# IRF7317_TR.net
KiCad netlist of a schematic drawn in Altium Designer
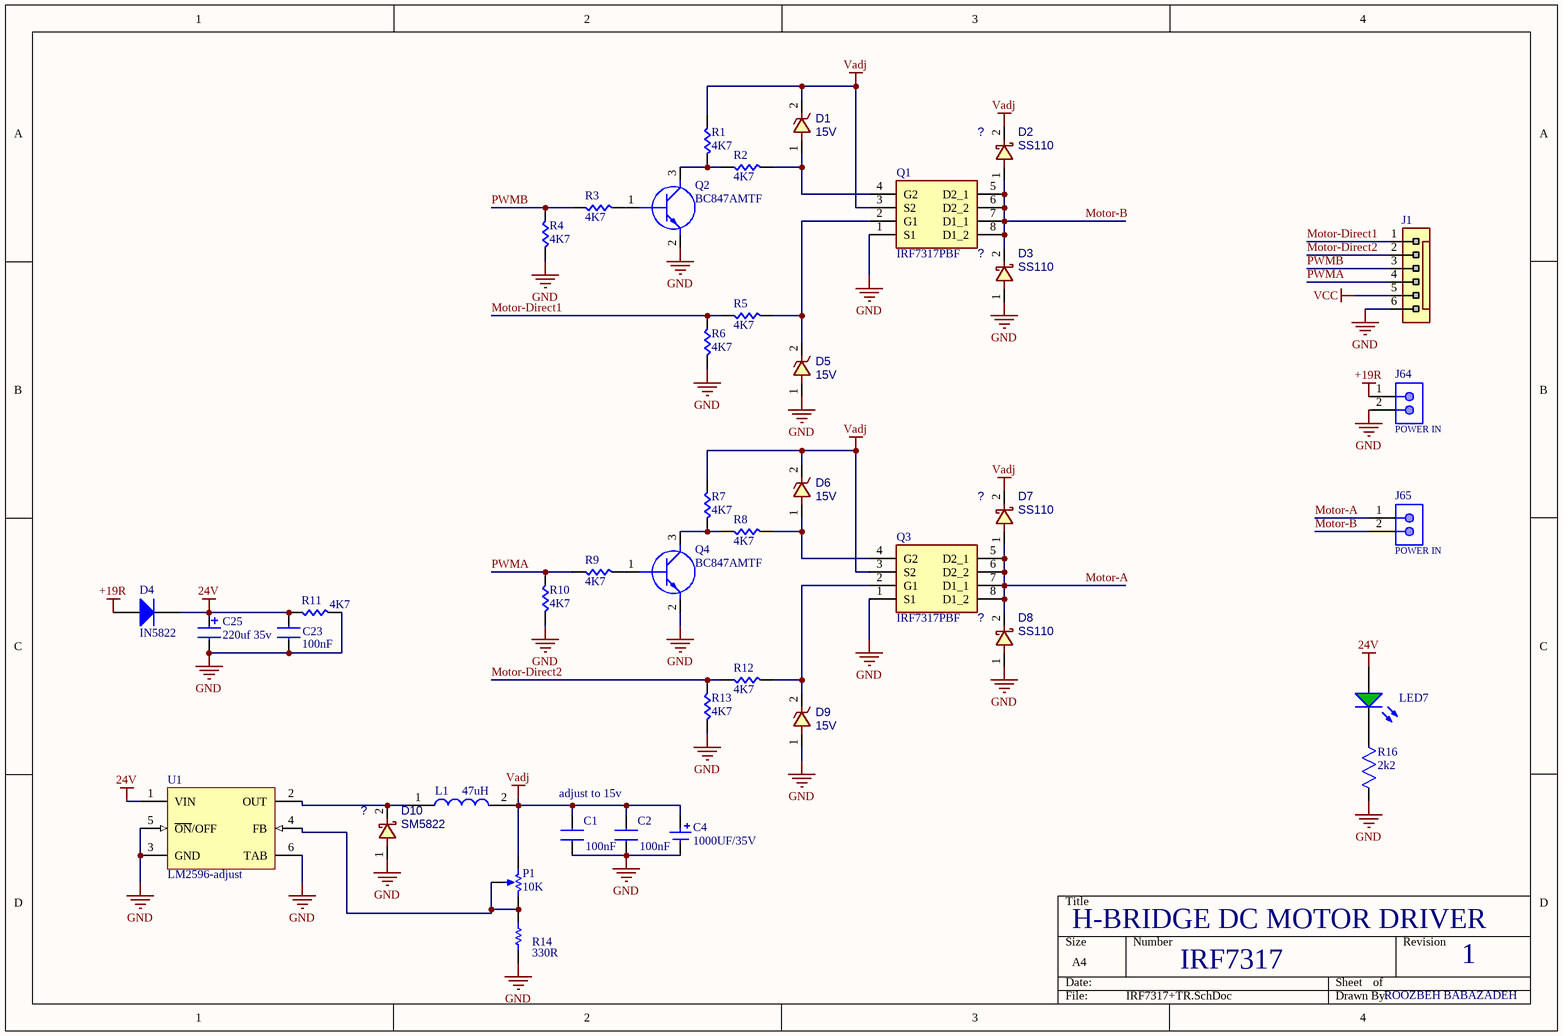
[diagram p0: IRF7317+TR.SchDoc]

(export (version "E")
  (design (tool "Eeschema 10.0.6"))
  (components
    (comp (ref "C1") (value "100nF") (footprint "C0805") (libsource (lib "OTHER") (part "C")))
    (comp (ref "C2") (value "100nF") (footprint "C0805") (libsource (lib "OTHER") (part "C")))
    (comp (ref "C4")
      (value "1000UF/35V")
      (footprint "C_EL_12X25")
      (libsource (lib "OTHER") (part "CAP_ELECTRO_POLIMER"))
    )
    (comp (ref "C23") (value "100nF") (footprint "C0805") (libsource (lib "OTHER") (part "C")))
    (comp (ref "C25") (value "220uf 35v") (footprint "C_EL_10X12") (libsource (lib "OTHER") (part "CAP3528")))
    (comp (ref "D1")
      (value "15V")
      (footprint "D_SOD80")
      (description "DIODE, ZENER, 3W, 5.6V")
      (fields (field (name "MANF") "MCC") (field (name "MANF_P#") "3SMAJ5919B-TP"))
      (libsource (lib "diode") (part "ZENER"))
    )
    (comp (ref "D2")
      (value "SS110")
      (footprint "D_SMA")
      (description "DIODE, SCHOTTKY, 40V, 1A")
      (fields
        (field (name "MANF") "DIODES")
        (field (name "MANF_P#") "1N5819HW-7-F")
        (field (name "ALTIUM_VALUE") "?")
      )
      (libsource (lib "diode") (part "SCHOTTKY"))
    )
    (comp (ref "D3")
      (value "SS110")
      (footprint "D_SMA")
      (description "DIODE, SCHOTTKY, 40V, 1A")
      (fields
        (field (name "MANF") "DIODES")
        (field (name "MANF_P#") "1N5819HW-7-F")
        (field (name "ALTIUM_VALUE") "?")
      )
      (libsource (lib "diode") (part "SCHOTTKY"))
    )
    (comp (ref "D4")
      (value "IN5822")
      (footprint "D_SMB")
      (description "1 Amp General Purpose Rectifier")
      (fields (field (name "PUBLISHER") "Altium Limited"))
      (libsource (lib "Miscellaneous Devices") (part "Diode 1N4005"))
    )
    (comp (ref "D5")
      (value "15V")
      (footprint "D_SOD80")
      (description "DIODE, ZENER, 3W, 5.6V")
      (fields (field (name "MANF") "MCC") (field (name "MANF_P#") "3SMAJ5919B-TP"))
      (libsource (lib "diode") (part "ZENER"))
    )
    (comp (ref "D6")
      (value "15V")
      (footprint "D_SOD80")
      (description "DIODE, ZENER, 3W, 5.6V")
      (fields (field (name "MANF") "MCC") (field (name "MANF_P#") "3SMAJ5919B-TP"))
      (libsource (lib "diode") (part "ZENER"))
    )
    (comp (ref "D7")
      (value "SS110")
      (footprint "D_SMA")
      (description "DIODE, SCHOTTKY, 40V, 1A")
      (fields
        (field (name "MANF") "DIODES")
        (field (name "MANF_P#") "1N5819HW-7-F")
        (field (name "ALTIUM_VALUE") "?")
      )
      (libsource (lib "diode") (part "SCHOTTKY"))
    )
    (comp (ref "D8")
      (value "SS110")
      (footprint "D_SMA")
      (description "DIODE, SCHOTTKY, 40V, 1A")
      (fields
        (field (name "MANF") "DIODES")
        (field (name "MANF_P#") "1N5819HW-7-F")
        (field (name "ALTIUM_VALUE") "?")
      )
      (libsource (lib "diode") (part "SCHOTTKY"))
    )
    (comp (ref "D9")
      (value "15V")
      (footprint "D_SOD80")
      (description "DIODE, ZENER, 3W, 5.6V")
      (fields (field (name "MANF") "MCC") (field (name "MANF_P#") "3SMAJ5919B-TP"))
      (libsource (lib "diode") (part "ZENER"))
    )
    (comp (ref "D10")
      (value "SM5822")
      (footprint "D_SMB")
      (description "DIODE, SCHOTTKY, 40V, 1A")
      (fields
        (field (name "MANF") "DIODES")
        (field (name "MANF_P#") "1N5819HW-7-F")
        (field (name "ALTIUM_VALUE") "?")
      )
      (libsource (lib "diode") (part "SCHOTTKY"))
    )
    (comp (ref "J1")
      (value "HDRWF_6")
      (footprint "WF_6")
      (description "Header, WF, Pitch: 2.54mm")
      (libsource (lib "xh-xhr-wf-hhdr-hh6r") (part "HDRWF_6"))
    )
    (comp (ref "J64")
      (value "POWER IN")
      (footprint "PWL_2")
      (description "WR-PHD Pin Header, THT, pitch 2.54mm, Single Row, Vertical, 2pin")
      (fields (field (name "PART NUMBER") "61300211121") (field (name "PUBLISHER") "Wurth Elektronik"))
      (libsource (lib "sip m") (part "sip 2"))
    )
    (comp (ref "J65")
      (value "POWER IN")
      (footprint "PWL_2")
      (description "WR-PHD Pin Header, THT, pitch 2.54mm, Single Row, Vertical, 2pin")
      (fields (field (name "PART NUMBER") "61300211121") (field (name "PUBLISHER") "Wurth Elektronik"))
      (libsource (lib "sip m") (part "sip 2"))
    )
    (comp (ref "L1")
      (value "47uH")
      (footprint "CDRH127LDNP560MC-12*12")
      (description "Inductor")
      (fields
        (field (name "MANUFACTURER_PART_NUMBER") "CDRH127/LDNP-560MC")
        (field (name "MOUSER PART NUMBER") "851-CDRH127LDNP560MC")
      )
      (libsource (lib "*") (part "CDRH127_LDNP-560MC"))
    )
    (comp (ref "LED7") (value "~") (footprint "LED1206RED") (libsource (lib "OTHER") (part "LED3mm")))
    (comp (ref "P1")
      (value "10K")
      (footprint "POT_3296W")
      (description "Potentiometer")
      (libsource (lib "My_LIB") (part "Multi-Turn"))
    )
    (comp (ref "Q1")
      (value "IRF7317PBF")
      (footprint "SO_8")
      (description "Transistor")
      (fields (field (name "MOUSER PART NUMBER") "942-IRF7317PBF"))
      (libsource (lib "*") (part "IRF7317PBF"))
    )
    (comp (ref "Q2")
      (value "BC847AMTF")
      (footprint "SOT23")
      (description "Transistor BJT NPN")
      (fields (field (name "MOUSER PART NUMBER") "512-BC847AMTF"))
      (libsource (lib "*") (part "BC847AMTF"))
    )
    (comp (ref "Q3")
      (value "IRF7317PBF")
      (footprint "SO_8")
      (description "Transistor")
      (fields (field (name "MOUSER PART NUMBER") "942-IRF7317PBF"))
      (libsource (lib "*") (part "IRF7317PBF"))
    )
    (comp (ref "Q4")
      (value "BC847AMTF")
      (footprint "SOT23")
      (description "Transistor BJT NPN")
      (fields (field (name "MOUSER PART NUMBER") "512-BC847AMTF"))
      (libsource (lib "*") (part "BC847AMTF"))
    )
    (comp (ref "R1") (value "4K7") (footprint "R0805") (libsource (lib "OTHER") (part "R")))
    (comp (ref "R2") (value "4K7") (footprint "R0805") (libsource (lib "OTHER") (part "R")))
    (comp (ref "R3") (value "4K7") (footprint "R0805") (libsource (lib "OTHER") (part "R")))
    (comp (ref "R4") (value "4K7") (footprint "R0805") (libsource (lib "OTHER") (part "R")))
    (comp (ref "R5") (value "4K7") (footprint "R0805") (libsource (lib "OTHER") (part "R")))
    (comp (ref "R6") (value "4K7") (footprint "R0805") (libsource (lib "OTHER") (part "R")))
    (comp (ref "R7") (value "4K7") (footprint "R0805") (libsource (lib "OTHER") (part "R")))
    (comp (ref "R8") (value "4K7") (footprint "R0805") (libsource (lib "OTHER") (part "R")))
    (comp (ref "R9") (value "4K7") (footprint "R0805") (libsource (lib "OTHER") (part "R")))
    (comp (ref "R10") (value "4K7") (footprint "R0805") (libsource (lib "OTHER") (part "R")))
    (comp (ref "R11") (value "4K7") (footprint "R0805") (libsource (lib "OTHER") (part "R")))
    (comp (ref "R12") (value "4K7") (footprint "R0805") (libsource (lib "OTHER") (part "R")))
    (comp (ref "R13") (value "4K7") (footprint "R0805") (libsource (lib "OTHER") (part "R")))
    (comp (ref "R14")
      (value "330R")
      (footprint "R0805")
      (description "Resistor")
      (fields (field (name "PUBLISHER") "Altium Limited"))
      (libsource (lib "Miscellaneous Devices") (part "Res1"))
    )
    (comp (ref "R16") (value "2k2") (footprint "R0805") (libsource (lib "") (part "R_1")))
    (comp (ref "U1")
      (value "LM2596-adjust")
      (footprint "to-263-5 5d2pak LM2596S")
      (libsource (lib "POWER") (part "LM2596s"))
    )
  )
  (nets
    (net (code "1") (name "+19R") (class "Default")
      (node (ref "D4") (pin "1") (pinfunction "A_1") (pintype "passive"))
      (node (ref "J64") (pin "1") (pinfunction "1_1") (pintype "passive"))
    )
    (net (code "2") (name "/Motor-A") (class "Default")
      (node (ref "D7") (pin "1") (pinfunction "1_1") (pintype "passive"))
      (node (ref "D8") (pin "2") (pinfunction "2_2") (pintype "passive"))
      (node (ref "J65") (pin "1") (pinfunction "1_1") (pintype "passive"))
      (node (ref "Q3") (pin "5") (pinfunction "D2_1_5") (pintype "passive"))
      (node (ref "Q3") (pin "6") (pinfunction "D2_2_6") (pintype "passive"))
      (node (ref "Q3") (pin "7") (pinfunction "D1_1_7") (pintype "passive"))
      (node (ref "Q3") (pin "8") (pinfunction "D1_2_8") (pintype "passive"))
    )
    (net (code "3") (name "/Motor-B") (class "Default")
      (node (ref "D2") (pin "1") (pinfunction "1_1") (pintype "passive"))
      (node (ref "D3") (pin "2") (pinfunction "2_2") (pintype "passive"))
      (node (ref "J65") (pin "2") (pinfunction "2_2") (pintype "passive"))
      (node (ref "Q1") (pin "5") (pinfunction "D2_1_5") (pintype "passive"))
      (node (ref "Q1") (pin "6") (pinfunction "D2_2_6") (pintype "passive"))
      (node (ref "Q1") (pin "7") (pinfunction "D1_1_7") (pintype "passive"))
      (node (ref "Q1") (pin "8") (pinfunction "D1_2_8") (pintype "passive"))
    )
    (net (code "4") (name "/Motor-Direct1") (class "Default")
      (node (ref "J1") (pin "1") (pinfunction "1_1") (pintype "passive"))
      (node (ref "R5") (pin "2") (pintype "passive"))
      (node (ref "R6") (pin "1") (pintype "passive"))
    )
    (net (code "5") (name "/Motor-Direct2") (class "Default")
      (node (ref "J1") (pin "2") (pinfunction "2_2") (pintype "passive"))
      (node (ref "R12") (pin "2") (pintype "passive"))
      (node (ref "R13") (pin "1") (pintype "passive"))
    )
    (net (code "6") (name "/PWMA") (class "Default")
      (node (ref "J1") (pin "4") (pinfunction "4_4") (pintype "passive"))
      (node (ref "R10") (pin "2") (pintype "passive"))
      (node (ref "R9") (pin "1") (pintype "passive"))
    )
    (net (code "7") (name "/PWMB") (class "Default")
      (node (ref "J1") (pin "3") (pinfunction "3_3") (pintype "passive"))
      (node (ref "R3") (pin "1") (pintype "passive"))
      (node (ref "R4") (pin "2") (pintype "passive"))
    )
    (net (code "8") (name "24V") (class "Default")
      (node (ref "C23") (pin "2") (pintype "passive"))
      (node (ref "C25") (pin "1") (pinfunction "1_1") (pintype "passive"))
      (node (ref "D4") (pin "2") (pinfunction "K_2") (pintype "passive"))
      (node (ref "LED7") (pin "1") (pinfunction "A_1") (pintype "passive"))
      (node (ref "R11") (pin "2") (pintype "passive"))
      (node (ref "U1") (pin "1") (pinfunction "VIN_1") (pintype "power_in"))
    )
    (net (code "9") (name "GND") (class "Default")
      (node (ref "C1") (pin "1") (pintype "passive"))
      (node (ref "C2") (pin "1") (pintype "passive"))
      (node (ref "C23") (pin "1") (pintype "passive"))
      (node (ref "C25") (pin "2") (pinfunction "2_2") (pintype "passive"))
      (node (ref "C4") (pin "2") (pinfunction "2_2") (pintype "passive"))
      (node (ref "D10") (pin "1") (pinfunction "1_1") (pintype "passive"))
      (node (ref "D3") (pin "1") (pinfunction "1_1") (pintype "passive"))
      (node (ref "D5") (pin "1") (pinfunction "1_1") (pintype "passive"))
      (node (ref "D8") (pin "1") (pinfunction "1_1") (pintype "passive"))
      (node (ref "D9") (pin "1") (pinfunction "1_1") (pintype "passive"))
      (node (ref "J1") (pin "6") (pinfunction "6_6") (pintype "passive"))
      (node (ref "J64") (pin "2") (pinfunction "2_2") (pintype "passive"))
      (node (ref "Q1") (pin "1") (pinfunction "S1_1") (pintype "passive"))
      (node (ref "Q2") (pin "2") (pinfunction "E_2") (pintype "passive"))
      (node (ref "Q3") (pin "1") (pinfunction "S1_1") (pintype "passive"))
      (node (ref "Q4") (pin "2") (pinfunction "E_2") (pintype "passive"))
      (node (ref "R10") (pin "1") (pintype "passive"))
      (node (ref "R11") (pin "1") (pintype "passive"))
      (node (ref "R13") (pin "2") (pintype "passive"))
      (node (ref "R14") (pin "1") (pinfunction "1_1") (pintype "passive"))
      (node (ref "R16") (pin "2") (pintype "passive"))
      (node (ref "R4") (pin "1") (pintype "passive"))
      (node (ref "R6") (pin "2") (pintype "passive"))
      (node (ref "U1") (pin "3") (pinfunction "GND_3") (pintype "power_in"))
      (node (ref "U1") (pin "5") (pinfunction "~{ON}/OFF_5") (pintype "input"))
      (node (ref "U1") (pin "6") (pinfunction "TAB_6") (pintype "power_in"))
    )
    (net (code "10") (name "Net-(LED7-K)") (class "Default")
      (node (ref "LED7") (pin "2") (pinfunction "K_2") (pintype "passive"))
      (node (ref "R16") (pin "1") (pintype "passive"))
    )
    (net (code "11") (name "Net-(P1-TAP)") (class "Default")
      (node (ref "P1") (pin "1") (pinfunction "TOP_1") (pintype "passive"))
      (node (ref "P1") (pin "2") (pinfunction "TAP_2") (pintype "passive"))
      (node (ref "R14") (pin "2") (pinfunction "2_2") (pintype "passive"))
      (node (ref "U1") (pin "4") (pinfunction "FB_4") (pintype "input"))
    )
    (net (code "12") (name "Net-(Q1-G1)") (class "Default")
      (node (ref "D5") (pin "2") (pinfunction "2_2") (pintype "passive"))
      (node (ref "Q1") (pin "2") (pinfunction "G1_2") (pintype "passive"))
      (node (ref "R5") (pin "1") (pintype "passive"))
    )
    (net (code "13") (name "Net-(Q1-G2)") (class "Default")
      (node (ref "D1") (pin "1") (pinfunction "1_1") (pintype "passive"))
      (node (ref "Q1") (pin "4") (pinfunction "G2_4") (pintype "passive"))
      (node (ref "R2") (pin "1") (pintype "passive"))
    )
    (net (code "14") (name "Net-(Q2-B)") (class "Default")
      (node (ref "Q2") (pin "1") (pinfunction "B_1") (pintype "passive"))
      (node (ref "R3") (pin "2") (pintype "passive"))
    )
    (net (code "15") (name "Net-(Q2-C)") (class "Default")
      (node (ref "Q2") (pin "3") (pinfunction "C_3") (pintype "passive"))
      (node (ref "R1") (pin "2") (pintype "passive"))
      (node (ref "R2") (pin "2") (pintype "passive"))
    )
    (net (code "16") (name "Net-(Q3-G1)") (class "Default")
      (node (ref "D9") (pin "2") (pinfunction "2_2") (pintype "passive"))
      (node (ref "Q3") (pin "2") (pinfunction "G1_2") (pintype "passive"))
      (node (ref "R12") (pin "1") (pintype "passive"))
    )
    (net (code "17") (name "Net-(Q3-G2)") (class "Default")
      (node (ref "D6") (pin "1") (pinfunction "1_1") (pintype "passive"))
      (node (ref "Q3") (pin "4") (pinfunction "G2_4") (pintype "passive"))
      (node (ref "R8") (pin "1") (pintype "passive"))
    )
    (net (code "18") (name "Net-(Q4-B)") (class "Default")
      (node (ref "Q4") (pin "1") (pinfunction "B_1") (pintype "passive"))
      (node (ref "R9") (pin "2") (pintype "passive"))
    )
    (net (code "19") (name "Net-(Q4-C)") (class "Default")
      (node (ref "Q4") (pin "3") (pinfunction "C_3") (pintype "passive"))
      (node (ref "R7") (pin "2") (pintype "passive"))
      (node (ref "R8") (pin "2") (pintype "passive"))
    )
    (net (code "20") (name "Net-(U1-OUT)") (class "Default")
      (node (ref "D10") (pin "2") (pinfunction "2_2") (pintype "passive"))
      (node (ref "L1") (pin "1") (pinfunction "1_1") (pintype "passive"))
      (node (ref "U1") (pin "2") (pinfunction "OUT_2") (pintype "power_in"))
    )
    (net (code "21") (name "VCC") (class "Default")
      (node (ref "J1") (pin "5") (pinfunction "5_5") (pintype "passive"))
    )
    (net (code "22") (name "Vadj") (class "Default")
      (node (ref "C1") (pin "2") (pintype "passive"))
      (node (ref "C2") (pin "2") (pintype "passive"))
      (node (ref "C4") (pin "1") (pinfunction "1_1") (pintype "passive"))
      (node (ref "D1") (pin "2") (pinfunction "2_2") (pintype "passive"))
      (node (ref "D2") (pin "2") (pinfunction "2_2") (pintype "passive"))
      (node (ref "D6") (pin "2") (pinfunction "2_2") (pintype "passive"))
      (node (ref "D7") (pin "2") (pinfunction "2_2") (pintype "passive"))
      (node (ref "L1") (pin "2") (pinfunction "2_2") (pintype "passive"))
      (node (ref "P1") (pin "3") (pinfunction "BOT_3") (pintype "passive"))
      (node (ref "Q1") (pin "3") (pinfunction "S2_3") (pintype "passive"))
      (node (ref "Q3") (pin "3") (pinfunction "S2_3") (pintype "passive"))
      (node (ref "R1") (pin "1") (pintype "passive"))
      (node (ref "R7") (pin "1") (pintype "passive"))
    )
  )
)
